# Motor_Control.net
KiCad netlist of a schematic drawn in EAGLE
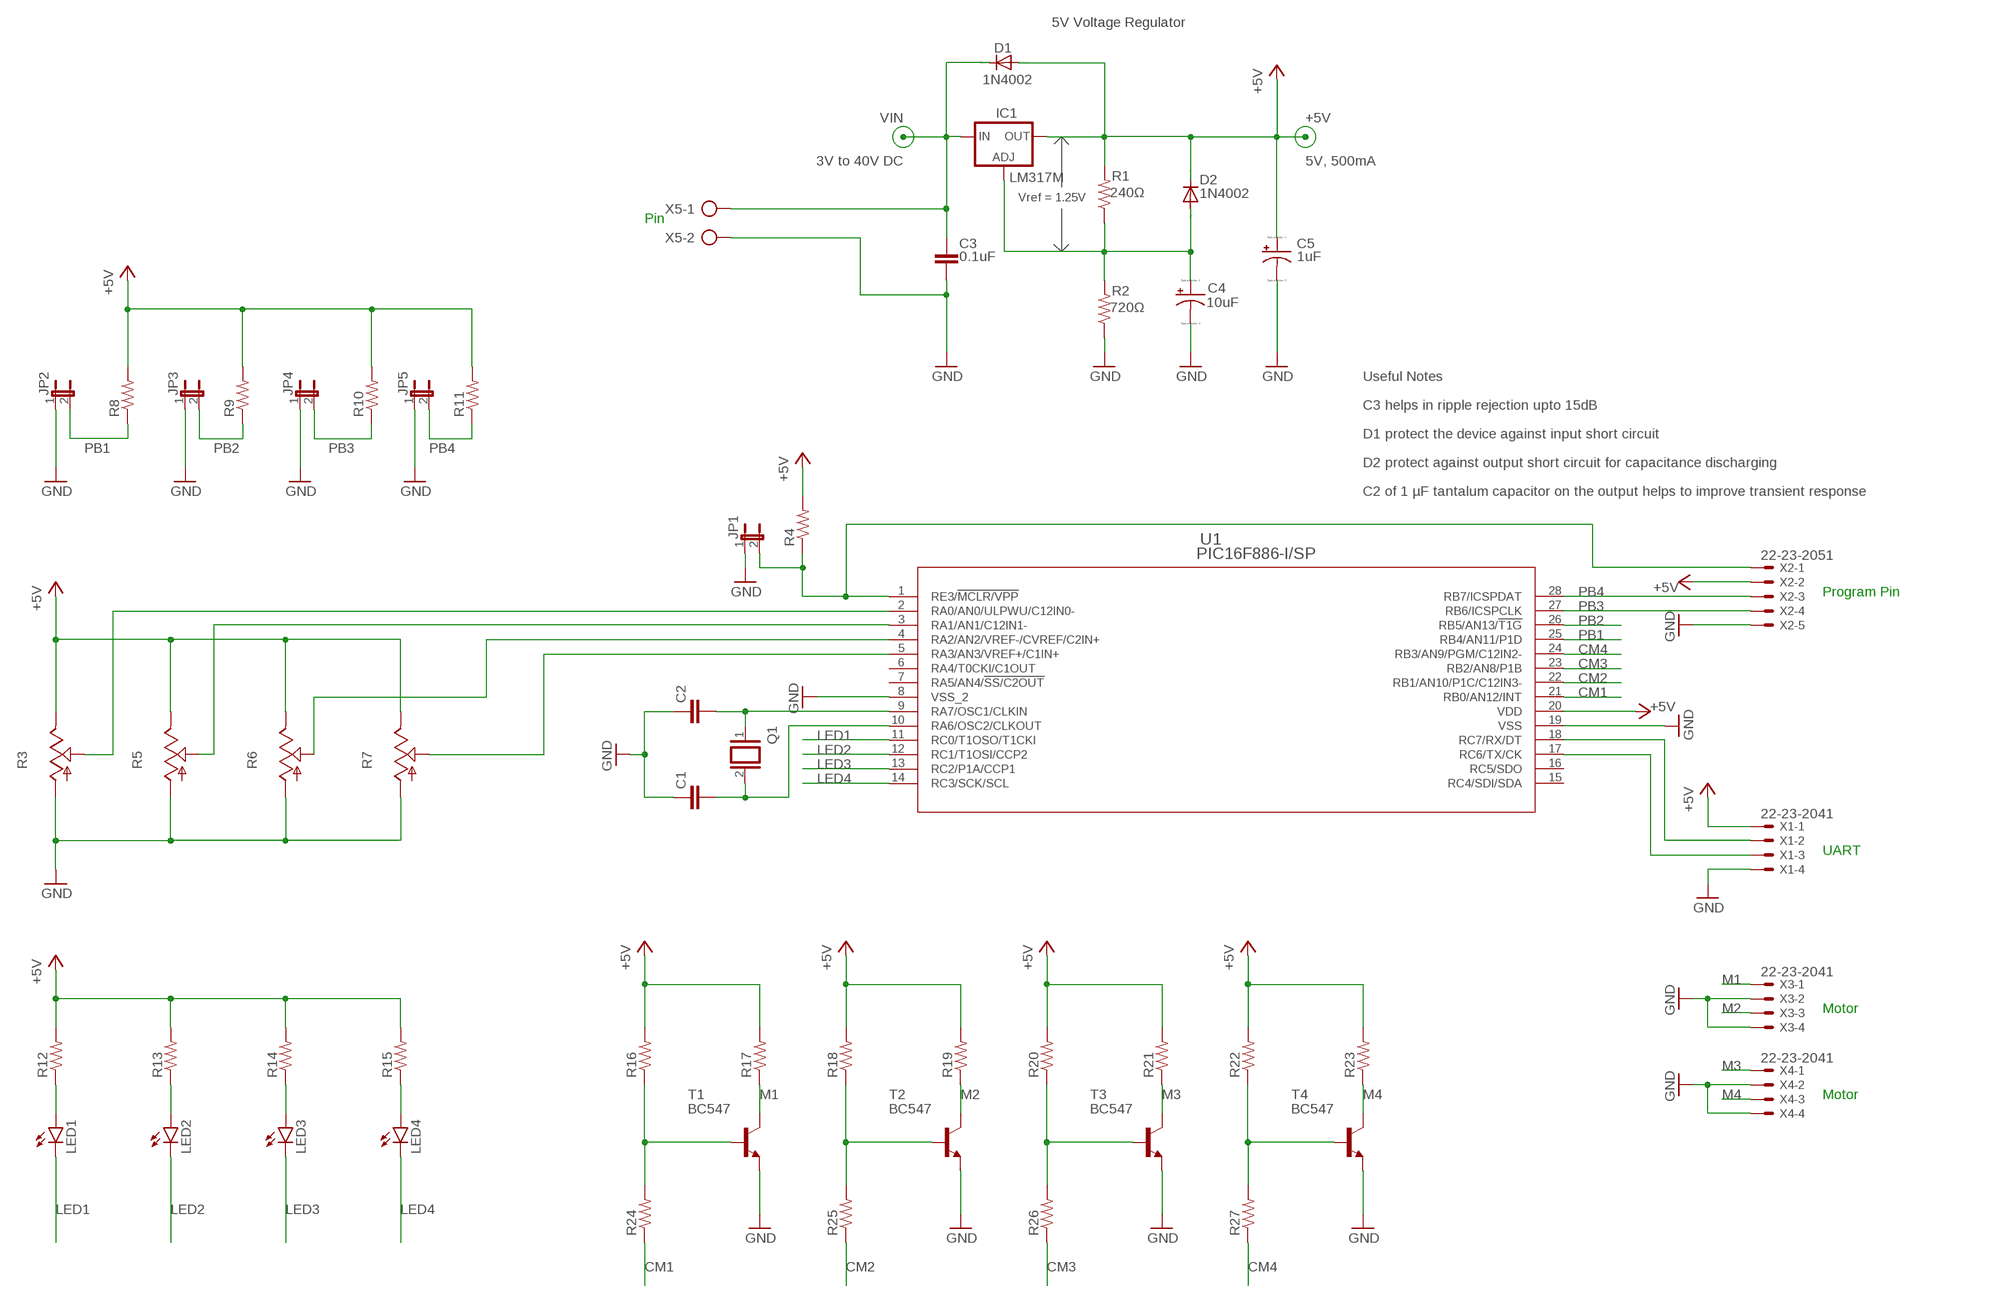
[diagram p0: schematic, sheet 1]

(export (version "E")
  (design (tool "Eeschema 10.0.6"))
  (components
    (comp (ref "C1")
      (value "C-EUC0805")
      (footprint "eagle-import:C0805")
      (libsource (lib "eagle-import") (part "C-EUC0805"))
    )
    (comp (ref "C2")
      (value "C-EUC0805")
      (footprint "eagle-import:C0805")
      (libsource (lib "eagle-import") (part "C-EUC0805"))
    )
    (comp (ref "C3")
      (value "0.1uF")
      (footprint "eagle-import:C075-052X106")
      (libsource (lib "eagle-import") (part "C-EU075-052X106"))
    )
    (comp (ref "C4")
      (value "10uF")
      (footprint "eagle-import:085CS_1AR")
      (libsource (lib "eagle-import") (part "CPOL-US085CS-1AR"))
    )
    (comp (ref "C5")
      (value "1uF")
      (footprint "eagle-import:085CS_1AR")
      (libsource (lib "eagle-import") (part "CPOL-US085CS-1AR"))
    )
    (comp (ref "D1")
      (value "1N4002")
      (footprint "eagle-import:DO41-10")
      (libsource (lib "eagle-import") (part "1N4004"))
    )
    (comp (ref "D2")
      (value "1N4002")
      (footprint "eagle-import:DO41-10")
      (libsource (lib "eagle-import") (part "1N4004"))
    )
    (comp (ref "IC1")
      (value "LM317MBSTT3")
      (footprint "eagle-import:SOT223")
      (fields (field (name "PARTNUMBER") "LM317M"))
      (libsource (lib "eagle-import") (part "LM317?MBSTT3"))
    )
    (comp (ref "JP1")
      (value "JP1E")
      (footprint "eagle-import:JP1")
      (libsource (lib "eagle-import") (part "JP1E"))
    )
    (comp (ref "JP2")
      (value "JP1E")
      (footprint "eagle-import:JP1")
      (libsource (lib "eagle-import") (part "JP1E"))
    )
    (comp (ref "JP3")
      (value "JP1E")
      (footprint "eagle-import:JP1")
      (libsource (lib "eagle-import") (part "JP1E"))
    )
    (comp (ref "JP4")
      (value "JP1E")
      (footprint "eagle-import:JP1")
      (libsource (lib "eagle-import") (part "JP1E"))
    )
    (comp (ref "JP5")
      (value "JP1E")
      (footprint "eagle-import:JP1")
      (libsource (lib "eagle-import") (part "JP1E"))
    )
    (comp (ref "LED1")
      (value "LED3MM")
      (footprint "eagle-import:LED3MM")
      (libsource (lib "eagle-import") (part "LED3MM"))
    )
    (comp (ref "LED2")
      (value "LED3MM")
      (footprint "eagle-import:LED3MM")
      (libsource (lib "eagle-import") (part "LED3MM"))
    )
    (comp (ref "LED3")
      (value "LED3MM")
      (footprint "eagle-import:LED3MM")
      (libsource (lib "eagle-import") (part "LED3MM"))
    )
    (comp (ref "LED4")
      (value "LED3MM")
      (footprint "eagle-import:LED3MM")
      (libsource (lib "eagle-import") (part "LED3MM"))
    )
    (comp (ref "Q1")
      (value "XTAL/S")
      (footprint "eagle-import:QS")
      (libsource (lib "eagle-import") (part "XTAL/S"))
    )
    (comp (ref "R1")
      (value "240Ω")
      (footprint "eagle-import:M0805")
      (libsource (lib "eagle-import") (part "resistor_348_R-US_M0805"))
    )
    (comp (ref "R2")
      (value "720Ω")
      (footprint "eagle-import:M0805")
      (libsource (lib "eagle-import") (part "resistor_348_R-US_M0805"))
    )
    (comp (ref "R3")
      (value "TRIM_US-LI15")
      (footprint "eagle-import:LI15")
      (libsource (lib "eagle-import") (part "TRIM_US-LI15"))
    )
    (comp (ref "R4")
      (value "R-US_0204/7")
      (footprint "eagle-import:0204_7")
      (libsource (lib "eagle-import") (part "R-US_0204/7"))
    )
    (comp (ref "R5")
      (value "TRIM_US-LI15")
      (footprint "eagle-import:LI15")
      (libsource (lib "eagle-import") (part "TRIM_US-LI15"))
    )
    (comp (ref "R6")
      (value "TRIM_US-LI15")
      (footprint "eagle-import:LI15")
      (libsource (lib "eagle-import") (part "TRIM_US-LI15"))
    )
    (comp (ref "R7")
      (value "TRIM_US-LI15")
      (footprint "eagle-import:LI15")
      (libsource (lib "eagle-import") (part "TRIM_US-LI15"))
    )
    (comp (ref "R8")
      (value "R-US_0204/7")
      (footprint "eagle-import:0204_7")
      (libsource (lib "eagle-import") (part "R-US_0204/7"))
    )
    (comp (ref "R9")
      (value "R-US_0204/7")
      (footprint "eagle-import:0204_7")
      (libsource (lib "eagle-import") (part "R-US_0204/7"))
    )
    (comp (ref "R10")
      (value "R-US_0204/7")
      (footprint "eagle-import:0204_7")
      (libsource (lib "eagle-import") (part "R-US_0204/7"))
    )
    (comp (ref "R11")
      (value "R-US_0204/7")
      (footprint "eagle-import:0204_7")
      (libsource (lib "eagle-import") (part "R-US_0204/7"))
    )
    (comp (ref "R12")
      (value "R-US_0204/7")
      (footprint "eagle-import:0204_7")
      (libsource (lib "eagle-import") (part "R-US_0204/7"))
    )
    (comp (ref "R13")
      (value "R-US_0204/7")
      (footprint "eagle-import:0204_7")
      (libsource (lib "eagle-import") (part "R-US_0204/7"))
    )
    (comp (ref "R14")
      (value "R-US_0204/7")
      (footprint "eagle-import:0204_7")
      (libsource (lib "eagle-import") (part "R-US_0204/7"))
    )
    (comp (ref "R15")
      (value "R-US_0204/7")
      (footprint "eagle-import:0204_7")
      (libsource (lib "eagle-import") (part "R-US_0204/7"))
    )
    (comp (ref "R16")
      (value "R-US_0204/7")
      (footprint "eagle-import:0204_7")
      (libsource (lib "eagle-import") (part "R-US_0204/7"))
    )
    (comp (ref "R17")
      (value "R-US_0204/7")
      (footprint "eagle-import:0204_7")
      (libsource (lib "eagle-import") (part "R-US_0204/7"))
    )
    (comp (ref "R18")
      (value "R-US_0204/7")
      (footprint "eagle-import:0204_7")
      (libsource (lib "eagle-import") (part "R-US_0204/7"))
    )
    (comp (ref "R19")
      (value "R-US_0204/7")
      (footprint "eagle-import:0204_7")
      (libsource (lib "eagle-import") (part "R-US_0204/7"))
    )
    (comp (ref "R20")
      (value "R-US_0204/7")
      (footprint "eagle-import:0204_7")
      (libsource (lib "eagle-import") (part "R-US_0204/7"))
    )
    (comp (ref "R21")
      (value "R-US_0204/7")
      (footprint "eagle-import:0204_7")
      (libsource (lib "eagle-import") (part "R-US_0204/7"))
    )
    (comp (ref "R22")
      (value "R-US_0204/7")
      (footprint "eagle-import:0204_7")
      (libsource (lib "eagle-import") (part "R-US_0204/7"))
    )
    (comp (ref "R23")
      (value "R-US_0204/7")
      (footprint "eagle-import:0204_7")
      (libsource (lib "eagle-import") (part "R-US_0204/7"))
    )
    (comp (ref "R24")
      (value "R-US_0204/7")
      (footprint "eagle-import:0204_7")
      (libsource (lib "eagle-import") (part "R-US_0204/7"))
    )
    (comp (ref "R25")
      (value "R-US_0204/7")
      (footprint "eagle-import:0204_7")
      (libsource (lib "eagle-import") (part "R-US_0204/7"))
    )
    (comp (ref "R26")
      (value "R-US_0204/7")
      (footprint "eagle-import:0204_7")
      (libsource (lib "eagle-import") (part "R-US_0204/7"))
    )
    (comp (ref "R27")
      (value "R-US_0204/7")
      (footprint "eagle-import:0204_7")
      (libsource (lib "eagle-import") (part "R-US_0204/7"))
    )
    (comp (ref "T1")
      (value "BC547")
      (footprint "eagle-import:TO92")
      (libsource (lib "eagle-import") (part "BC547"))
    )
    (comp (ref "T2")
      (value "BC547")
      (footprint "eagle-import:TO92")
      (libsource (lib "eagle-import") (part "BC547"))
    )
    (comp (ref "T3")
      (value "BC547")
      (footprint "eagle-import:TO92")
      (libsource (lib "eagle-import") (part "BC547"))
    )
    (comp (ref "T4")
      (value "BC547")
      (footprint "eagle-import:TO92")
      (libsource (lib "eagle-import") (part "BC547"))
    )
    (comp (ref "U1")
      (value "PIC16F886-I/SP")
      (footprint "eagle-import:SPDIP28_300MC_MCH")
      (fields (field (name "COPYRIGHT") "Copyright (C) 2022 Ultra Librarian. All rights reserved."))
      (libsource (lib "eagle-import") (part "PIC16F886-I/SP"))
    )
    (comp (ref "X1")
      (value "22-23-2041")
      (footprint "eagle-import:22-23-2041")
      (fields (field (name "MF") "MOLEX"))
      (libsource (lib "eagle-import") (part "22-23-2041"))
    )
    (comp (ref "X2")
      (value "22-23-2051")
      (footprint "eagle-import:22-23-2051")
      (fields (field (name "MF") "MOLEX"))
      (libsource (lib "eagle-import") (part "22-23-2051"))
    )
    (comp (ref "X3")
      (value "22-23-2041")
      (footprint "eagle-import:22-23-2041")
      (fields (field (name "MF") "MOLEX"))
      (libsource (lib "eagle-import") (part "22-23-2041"))
    )
    (comp (ref "X4")
      (value "22-23-2041")
      (footprint "eagle-import:22-23-2041")
      (fields (field (name "MF") "MOLEX"))
      (libsource (lib "eagle-import") (part "22-23-2041"))
    )
    (comp (ref "X5")
      (value "AK300/2")
      (footprint "eagle-import:AK300_2")
      (libsource (lib "eagle-import") (part "AK300/2"))
    )
  )
  (nets
    (net (code "1") (name "+5V") (class "Default")
      (node (ref "C5") (pin "+") (pinfunction "+_+") (pintype "passive"))
      (node (ref "D1") (pin "A") (pinfunction "A_A") (pintype "passive"))
      (node (ref "D2") (pin "C") (pinfunction "C_C") (pintype "passive"))
      (node (ref "IC1") (pin "4") (pinfunction "OUT_4") (pintype "passive"))
      (node (ref "R1") (pin "2") (pinfunction "2_2") (pintype "passive"))
      (node (ref "R10") (pin "2") (pinfunction "2_2") (pintype "passive"))
      (node (ref "R11") (pin "2") (pinfunction "2_2") (pintype "passive"))
      (node (ref "R12") (pin "2") (pinfunction "2_2") (pintype "passive"))
      (node (ref "R13") (pin "2") (pinfunction "2_2") (pintype "passive"))
      (node (ref "R14") (pin "2") (pinfunction "2_2") (pintype "passive"))
      (node (ref "R15") (pin "2") (pinfunction "2_2") (pintype "passive"))
      (node (ref "R16") (pin "2") (pinfunction "2_2") (pintype "passive"))
      (node (ref "R17") (pin "2") (pinfunction "2_2") (pintype "passive"))
      (node (ref "R18") (pin "2") (pinfunction "2_2") (pintype "passive"))
      (node (ref "R19") (pin "2") (pinfunction "2_2") (pintype "passive"))
      (node (ref "R20") (pin "2") (pinfunction "2_2") (pintype "passive"))
      (node (ref "R21") (pin "2") (pinfunction "2_2") (pintype "passive"))
      (node (ref "R22") (pin "2") (pinfunction "2_2") (pintype "passive"))
      (node (ref "R23") (pin "2") (pinfunction "2_2") (pintype "passive"))
      (node (ref "R3") (pin "E") (pinfunction "E_E") (pintype "passive"))
      (node (ref "R4") (pin "2") (pinfunction "2_2") (pintype "passive"))
      (node (ref "R5") (pin "E") (pinfunction "E_E") (pintype "passive"))
      (node (ref "R6") (pin "E") (pinfunction "E_E") (pintype "passive"))
      (node (ref "R7") (pin "E") (pinfunction "E_E") (pintype "passive"))
      (node (ref "R8") (pin "2") (pinfunction "2_2") (pintype "passive"))
      (node (ref "R9") (pin "2") (pinfunction "2_2") (pintype "passive"))
      (node (ref "U1") (pin "20") (pinfunction "VDD_20") (pintype "passive"))
      (node (ref "X1") (pin "1") (pinfunction "S_1") (pintype "passive"))
      (node (ref "X2") (pin "2") (pinfunction "S_2") (pintype "passive"))
    )
    (net (code "2") (name "/CM1") (class "Default")
      (node (ref "R24") (pin "1") (pinfunction "1_1") (pintype "passive"))
      (node (ref "U1") (pin "21") (pinfunction "RB0/AN12/INT_21") (pintype "passive"))
    )
    (net (code "3") (name "/CM2") (class "Default")
      (node (ref "R25") (pin "1") (pinfunction "1_1") (pintype "passive"))
      (node (ref "U1") (pin "22") (pinfunction "RB1/AN10/P1C/C12IN3-_22") (pintype "passive"))
    )
    (net (code "4") (name "/CM3") (class "Default")
      (node (ref "R26") (pin "1") (pinfunction "1_1") (pintype "passive"))
      (node (ref "U1") (pin "23") (pinfunction "RB2/AN8/P1B_23") (pintype "passive"))
    )
    (net (code "5") (name "/CM4") (class "Default")
      (node (ref "R27") (pin "1") (pinfunction "1_1") (pintype "passive"))
      (node (ref "U1") (pin "24") (pinfunction "RB3/AN9/PGM/C12IN2-_24") (pintype "passive"))
    )
    (net (code "6") (name "/LED1") (class "Default")
      (node (ref "LED1") (pin "K") (pinfunction "C_K") (pintype "passive"))
      (node (ref "U1") (pin "11") (pinfunction "RC0/T1OSO/T1CKI_11") (pintype "passive"))
    )
    (net (code "7") (name "/LED2") (class "Default")
      (node (ref "LED2") (pin "K") (pinfunction "C_K") (pintype "passive"))
      (node (ref "U1") (pin "12") (pinfunction "RC1/T1OSI/CCP2_12") (pintype "passive"))
    )
    (net (code "8") (name "/LED3") (class "Default")
      (node (ref "LED3") (pin "K") (pinfunction "C_K") (pintype "passive"))
      (node (ref "U1") (pin "13") (pinfunction "RC2/P1A/CCP1_13") (pintype "passive"))
    )
    (net (code "9") (name "/LED4") (class "Default")
      (node (ref "LED4") (pin "K") (pinfunction "C_K") (pintype "passive"))
      (node (ref "U1") (pin "14") (pinfunction "RC3/SCK/SCL_14") (pintype "passive"))
    )
    (net (code "10") (name "/M1") (class "Default")
      (node (ref "R17") (pin "1") (pinfunction "1_1") (pintype "passive"))
      (node (ref "T1") (pin "3") (pinfunction "C_3") (pintype "passive"))
      (node (ref "X3") (pin "1") (pinfunction "S_1") (pintype "passive"))
    )
    (net (code "11") (name "/M2") (class "Default")
      (node (ref "R19") (pin "1") (pinfunction "1_1") (pintype "passive"))
      (node (ref "T2") (pin "3") (pinfunction "C_3") (pintype "passive"))
      (node (ref "X3") (pin "3") (pinfunction "S_3") (pintype "passive"))
    )
    (net (code "12") (name "/M3") (class "Default")
      (node (ref "R21") (pin "1") (pinfunction "1_1") (pintype "passive"))
      (node (ref "T3") (pin "3") (pinfunction "C_3") (pintype "passive"))
      (node (ref "X4") (pin "1") (pinfunction "S_1") (pintype "passive"))
    )
    (net (code "13") (name "/M4") (class "Default")
      (node (ref "R23") (pin "1") (pinfunction "1_1") (pintype "passive"))
      (node (ref "T4") (pin "3") (pinfunction "C_3") (pintype "passive"))
      (node (ref "X4") (pin "3") (pinfunction "S_3") (pintype "passive"))
    )
    (net (code "14") (name "/PB1") (class "Default")
      (node (ref "JP2") (pin "2") (pinfunction "2_2") (pintype "passive"))
      (node (ref "R8") (pin "1") (pinfunction "1_1") (pintype "passive"))
      (node (ref "U1") (pin "25") (pinfunction "RB4/AN11/P1D_25") (pintype "passive"))
    )
    (net (code "15") (name "/PB2") (class "Default")
      (node (ref "JP3") (pin "2") (pinfunction "2_2") (pintype "passive"))
      (node (ref "R9") (pin "1") (pinfunction "1_1") (pintype "passive"))
      (node (ref "U1") (pin "26") (pinfunction "RB5/AN13/~{T1G}_26") (pintype "passive"))
    )
    (net (code "16") (name "/PB3") (class "Default")
      (node (ref "JP4") (pin "2") (pinfunction "2_2") (pintype "passive"))
      (node (ref "R10") (pin "1") (pinfunction "1_1") (pintype "passive"))
      (node (ref "U1") (pin "27") (pinfunction "RB6/ICSPCLK_27") (pintype "passive"))
      (node (ref "X2") (pin "4") (pinfunction "S_4") (pintype "passive"))
    )
    (net (code "17") (name "/PB4") (class "Default")
      (node (ref "JP5") (pin "2") (pinfunction "2_2") (pintype "passive"))
      (node (ref "R11") (pin "1") (pinfunction "1_1") (pintype "passive"))
      (node (ref "U1") (pin "28") (pinfunction "RB7/ICSPDAT_28") (pintype "passive"))
      (node (ref "X2") (pin "3") (pinfunction "S_3") (pintype "passive"))
    )
    (net (code "18") (name "/VIN") (class "Default")
      (node (ref "C3") (pin "1") (pinfunction "1_1") (pintype "passive"))
      (node (ref "D1") (pin "C") (pinfunction "C_C") (pintype "passive"))
      (node (ref "IC1") (pin "3") (pinfunction "IN_3") (pintype "input"))
      (node (ref "X5") (pin "1") (pinfunction "KL_1") (pintype "passive"))
    )
    (net (code "19") (name "GND") (class "Default")
      (node (ref "C1") (pin "1") (pinfunction "1_1") (pintype "passive"))
      (node (ref "C2") (pin "1") (pinfunction "1_1") (pintype "passive"))
      (node (ref "C3") (pin "2") (pinfunction "2_2") (pintype "passive"))
      (node (ref "C4") (pin "-") (pinfunction "-_-") (pintype "passive"))
      (node (ref "C5") (pin "-") (pinfunction "-_-") (pintype "passive"))
      (node (ref "JP1") (pin "1") (pinfunction "1_1") (pintype "passive"))
      (node (ref "JP2") (pin "1") (pinfunction "1_1") (pintype "passive"))
      (node (ref "JP3") (pin "1") (pinfunction "1_1") (pintype "passive"))
      (node (ref "JP4") (pin "1") (pinfunction "1_1") (pintype "passive"))
      (node (ref "JP5") (pin "1") (pinfunction "1_1") (pintype "passive"))
      (node (ref "R2") (pin "1") (pinfunction "1_1") (pintype "passive"))
      (node (ref "R3") (pin "A") (pinfunction "A_A") (pintype "passive"))
      (node (ref "R5") (pin "A") (pinfunction "A_A") (pintype "passive"))
      (node (ref "R6") (pin "A") (pinfunction "A_A") (pintype "passive"))
      (node (ref "R7") (pin "A") (pinfunction "A_A") (pintype "passive"))
      (node (ref "T1") (pin "1") (pinfunction "E_1") (pintype "passive"))
      (node (ref "T2") (pin "1") (pinfunction "E_1") (pintype "passive"))
      (node (ref "T3") (pin "1") (pinfunction "E_1") (pintype "passive"))
      (node (ref "T4") (pin "1") (pinfunction "E_1") (pintype "passive"))
      (node (ref "U1") (pin "19") (pinfunction "VSS_19") (pintype "passive"))
      (node (ref "U1") (pin "8") (pinfunction "VSS_2_8") (pintype "passive"))
      (node (ref "X1") (pin "4") (pinfunction "S_4") (pintype "passive"))
      (node (ref "X2") (pin "5") (pinfunction "S_5") (pintype "passive"))
      (node (ref "X3") (pin "2") (pinfunction "S_2") (pintype "passive"))
      (node (ref "X3") (pin "4") (pinfunction "S_4") (pintype "passive"))
      (node (ref "X4") (pin "2") (pinfunction "S_2") (pintype "passive"))
      (node (ref "X4") (pin "4") (pinfunction "S_4") (pintype "passive"))
      (node (ref "X5") (pin "2") (pinfunction "KL_2") (pintype "passive"))
    )
    (net (code "20") (name "Net-(IC1-ADJ)") (class "Default")
      (node (ref "C4") (pin "+") (pinfunction "+_+") (pintype "passive"))
      (node (ref "D2") (pin "A") (pinfunction "A_A") (pintype "passive"))
      (node (ref "IC1") (pin "1") (pinfunction "ADJ_1") (pintype "input"))
      (node (ref "R1") (pin "1") (pinfunction "1_1") (pintype "passive"))
      (node (ref "R2") (pin "2") (pinfunction "2_2") (pintype "passive"))
    )
    (net (code "21") (name "Net-(LED1-PadA)") (class "Default")
      (node (ref "LED1") (pin "A") (pinfunction "A_A") (pintype "passive"))
      (node (ref "R12") (pin "1") (pinfunction "1_1") (pintype "passive"))
    )
    (net (code "22") (name "Net-(LED2-PadA)") (class "Default")
      (node (ref "LED2") (pin "A") (pinfunction "A_A") (pintype "passive"))
      (node (ref "R13") (pin "1") (pinfunction "1_1") (pintype "passive"))
    )
    (net (code "23") (name "Net-(LED3-PadA)") (class "Default")
      (node (ref "LED3") (pin "A") (pinfunction "A_A") (pintype "passive"))
      (node (ref "R14") (pin "1") (pinfunction "1_1") (pintype "passive"))
    )
    (net (code "24") (name "Net-(LED4-PadA)") (class "Default")
      (node (ref "LED4") (pin "A") (pinfunction "A_A") (pintype "passive"))
      (node (ref "R15") (pin "1") (pinfunction "1_1") (pintype "passive"))
    )
    (net (code "25") (name "Net-(T1-B)") (class "Default")
      (node (ref "R16") (pin "1") (pinfunction "1_1") (pintype "passive"))
      (node (ref "R24") (pin "2") (pinfunction "2_2") (pintype "passive"))
      (node (ref "T1") (pin "2") (pinfunction "B_2") (pintype "passive"))
    )
    (net (code "26") (name "Net-(T2-B)") (class "Default")
      (node (ref "R18") (pin "1") (pinfunction "1_1") (pintype "passive"))
      (node (ref "R25") (pin "2") (pinfunction "2_2") (pintype "passive"))
      (node (ref "T2") (pin "2") (pinfunction "B_2") (pintype "passive"))
    )
    (net (code "27") (name "Net-(T3-B)") (class "Default")
      (node (ref "R20") (pin "1") (pinfunction "1_1") (pintype "passive"))
      (node (ref "R26") (pin "2") (pinfunction "2_2") (pintype "passive"))
      (node (ref "T3") (pin "2") (pinfunction "B_2") (pintype "passive"))
    )
    (net (code "28") (name "Net-(T4-B)") (class "Default")
      (node (ref "R22") (pin "1") (pinfunction "1_1") (pintype "passive"))
      (node (ref "R27") (pin "2") (pinfunction "2_2") (pintype "passive"))
      (node (ref "T4") (pin "2") (pinfunction "B_2") (pintype "passive"))
    )
    (net (code "29") (name "Net-(U1-RA0{slash}AN0{slash}ULPWU{slash}C12IN0-)") (class "Default")
      (node (ref "R3") (pin "S") (pinfunction "S_S") (pintype "passive"))
      (node (ref "U1") (pin "2") (pinfunction "RA0/AN0/ULPWU/C12IN0-_2") (pintype "passive"))
    )
    (net (code "30") (name "Net-(U1-RA1{slash}AN1{slash}C12IN1-)") (class "Default")
      (node (ref "R5") (pin "S") (pinfunction "S_S") (pintype "passive"))
      (node (ref "U1") (pin "3") (pinfunction "RA1/AN1/C12IN1-_3") (pintype "passive"))
    )
    (net (code "31") (name "Net-(U1-RA2{slash}AN2{slash}VREF-{slash}CVREF{slash}C2IN+)") (class "Default")
      (node (ref "R6") (pin "S") (pinfunction "S_S") (pintype "passive"))
      (node (ref "U1") (pin "4") (pinfunction "RA2/AN2/VREF-/CVREF/C2IN+_4") (pintype "passive"))
    )
    (net (code "32") (name "Net-(U1-RA3{slash}AN3{slash}VREF+{slash}C1IN+)") (class "Default")
      (node (ref "R7") (pin "S") (pinfunction "S_S") (pintype "passive"))
      (node (ref "U1") (pin "5") (pinfunction "RA3/AN3/VREF+/C1IN+_5") (pintype "passive"))
    )
    (net (code "33") (name "Net-(U1-RA6{slash}OSC2{slash}CLKOUT)") (class "Default")
      (node (ref "C1") (pin "2") (pinfunction "2_2") (pintype "passive"))
      (node (ref "Q1") (pin "2") (pinfunction "2_2") (pintype "passive"))
      (node (ref "U1") (pin "10") (pinfunction "RA6/OSC2/CLKOUT_10") (pintype "passive"))
    )
    (net (code "34") (name "Net-(U1-RA7{slash}OSC1{slash}CLKIN)") (class "Default")
      (node (ref "C2") (pin "2") (pinfunction "2_2") (pintype "passive"))
      (node (ref "Q1") (pin "1") (pinfunction "1_1") (pintype "passive"))
      (node (ref "U1") (pin "9") (pinfunction "RA7/OSC1/CLKIN_9") (pintype "passive"))
    )
    (net (code "35") (name "Net-(U1-RC6{slash}TX{slash}CK)") (class "Default")
      (node (ref "U1") (pin "17") (pinfunction "RC6/TX/CK_17") (pintype "passive"))
      (node (ref "X1") (pin "3") (pinfunction "S_3") (pintype "passive"))
    )
    (net (code "36") (name "Net-(U1-RC7{slash}RX{slash}DT)") (class "Default")
      (node (ref "U1") (pin "18") (pinfunction "RC7/RX/DT_18") (pintype "passive"))
      (node (ref "X1") (pin "2") (pinfunction "S_2") (pintype "passive"))
    )
    (net (code "37") (name "Net-(U1-RE3{slash}~{MCLR{slash}VPP})") (class "Default")
      (node (ref "JP1") (pin "2") (pinfunction "2_2") (pintype "passive"))
      (node (ref "R4") (pin "1") (pinfunction "1_1") (pintype "passive"))
      (node (ref "U1") (pin "1") (pinfunction "RE3/~{MCLR/VPP}_1") (pintype "passive"))
      (node (ref "X2") (pin "1") (pinfunction "S_1") (pintype "passive"))
    )
    (net (code "38") (name "unconnected-(U1-RA4{slash}T0CKI{slash}C1OUT-Pad6)") (class "Default")
      (node (ref "U1") (pin "6") (pinfunction "RA4/T0CKI/C1OUT_6") (pintype "passive"))
    )
    (net (code "39") (name "unconnected-(U1-RA5{slash}AN4{slash}~{SS{slash}C2OUT}-Pad7)") (class "Default")
      (node (ref "U1") (pin "7") (pinfunction "RA5/AN4/~{SS/C2OUT}_7") (pintype "passive"))
    )
    (net (code "40") (name "unconnected-(U1-RC4{slash}SDI{slash}SDA-Pad15)") (class "Default")
      (node (ref "U1") (pin "15") (pinfunction "RC4/SDI/SDA_15") (pintype "passive"))
    )
    (net (code "41") (name "unconnected-(U1-RC5{slash}SDO-Pad16)") (class "Default")
      (node (ref "U1") (pin "16") (pinfunction "RC5/SDO_16") (pintype "passive"))
    )
  )
)
